# client_board.net
KiCad netlist of a schematic drawn in EAGLE
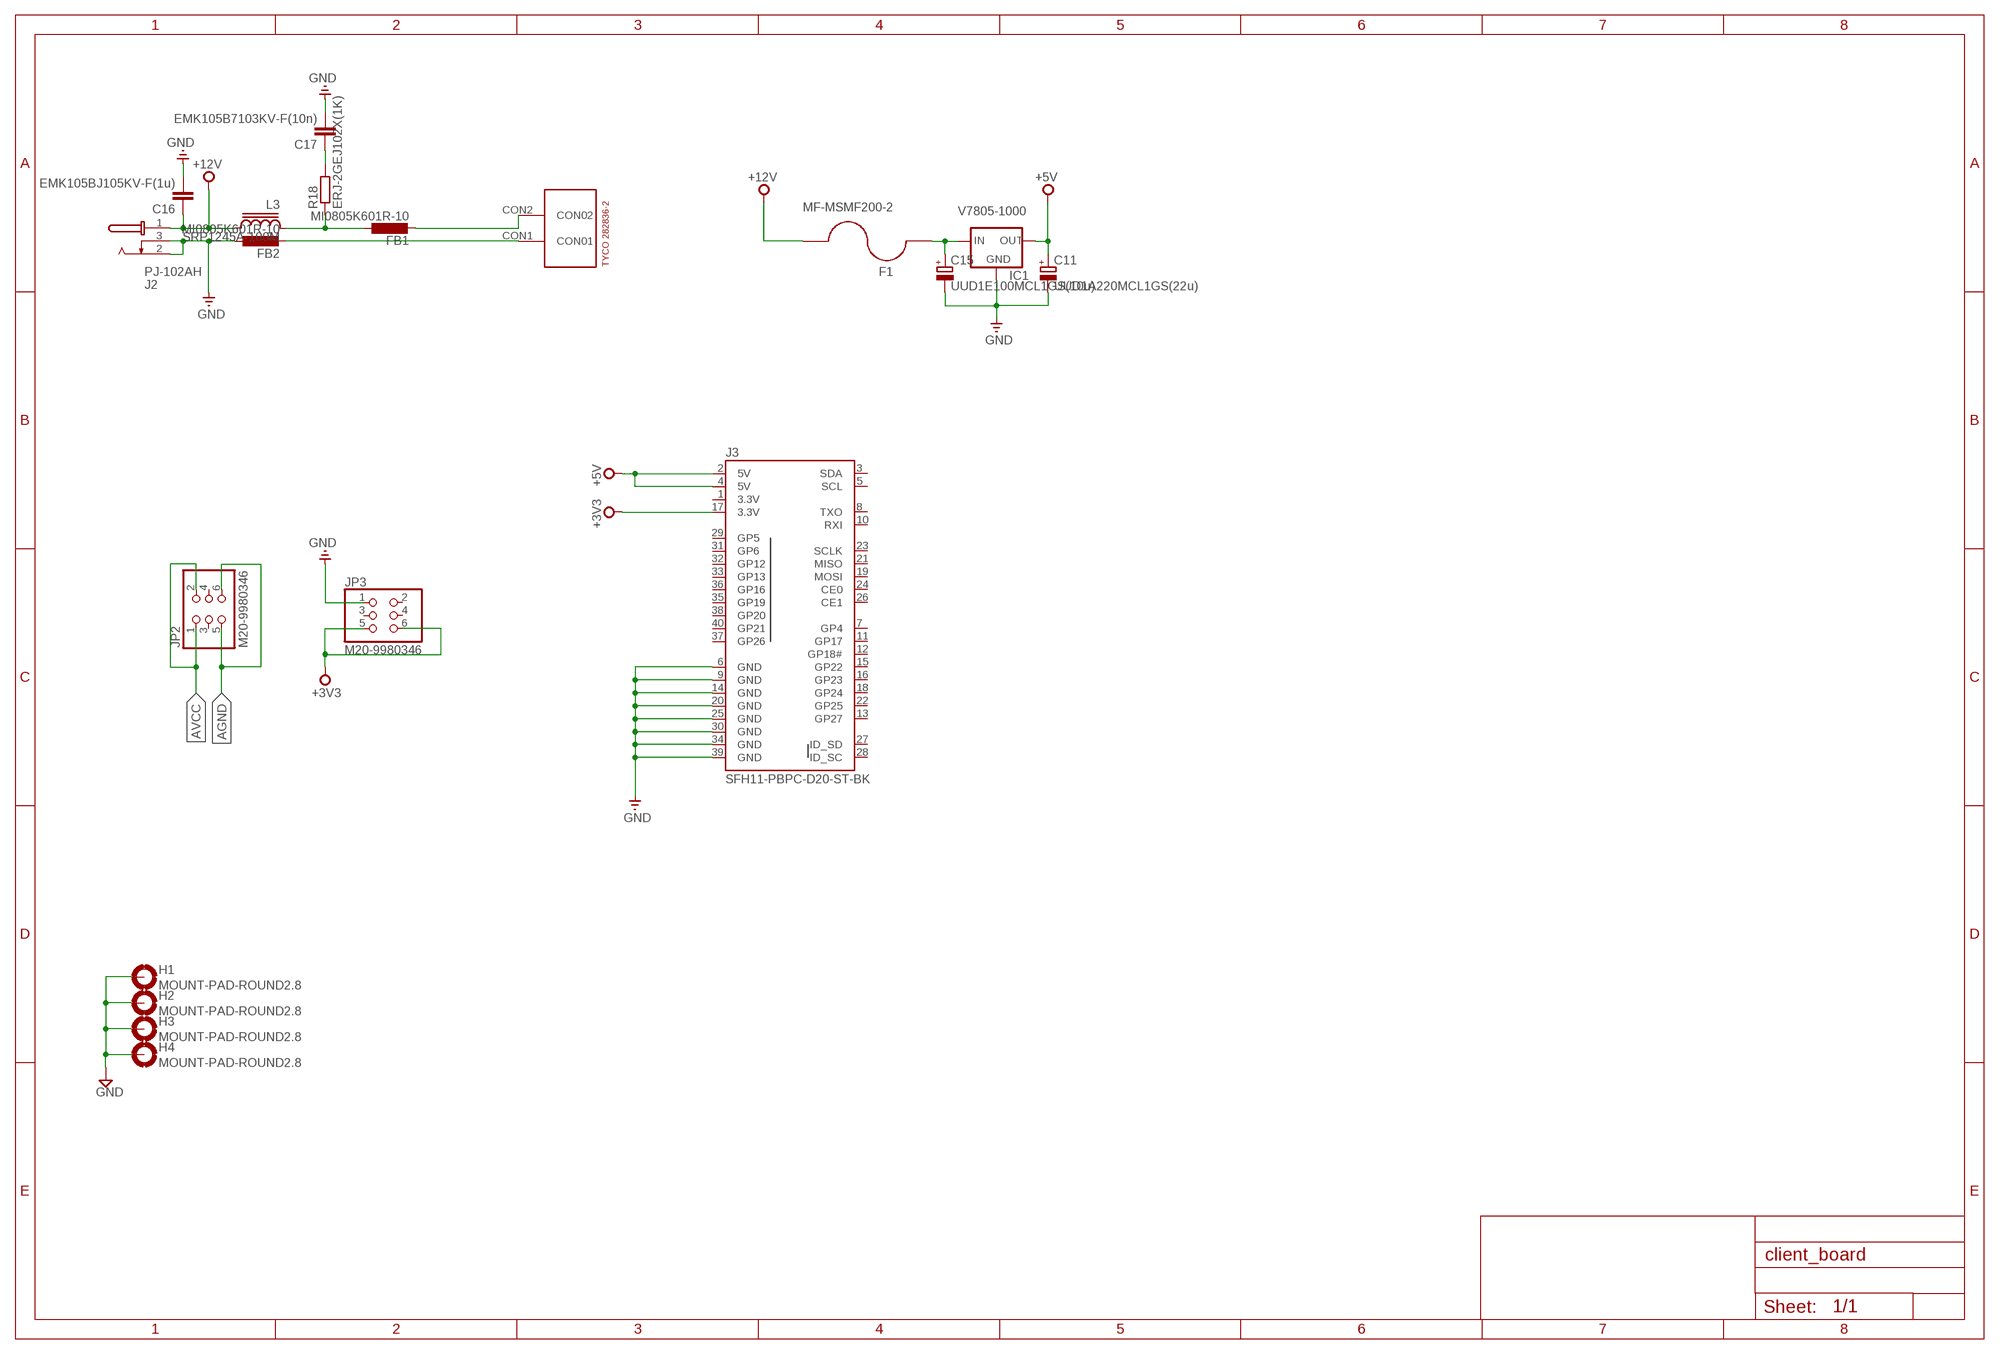
[diagram p0: schematic, sheet 1]

(export (version "E")
  (design (tool "Eeschema 10.0.6"))
  (components
    (comp (ref "C11")
      (value "UUD1A220MCL1GS(22u)")
      (footprint "eagle-import:153CLV-0405")
      (libsource (lib "eagle-import") (part "CPOL-EU153CLV-0405"))
    )
    (comp (ref "C15")
      (value "UUD1E100MCL1GS(10u)")
      (footprint "eagle-import:153CLV-0405")
      (libsource (lib "eagle-import") (part "CPOL-EU153CLV-0405"))
    )
    (comp (ref "C16")
      (value "EMK105BJ105KV-F(1u)")
      (footprint "eagle-import:C0402")
      (libsource (lib "eagle-import") (part "C-EUC0402"))
    )
    (comp (ref "C17")
      (value "EMK105B7103KV-F(10n)")
      (footprint "eagle-import:C0402")
      (libsource (lib "eagle-import") (part "C-EUC0402"))
    )
    (comp (ref "F1")
      (value "MF-MSMF200-2")
      (footprint "eagle-import:1812")
      (fields (field (name "MANUFACTURER") "Bourns Inc.") (field (name "PART_NUMBER") "MF-MSMF075/24-2"))
      (libsource (lib "eagle-import") (part "MF-MSMF?075/24"))
    )
    (comp (ref "FB1")
      (value "MI0805K601R-10")
      (footprint "eagle-import:L5650M")
      (libsource (lib "eagle-import") (part "L-EUL5650M"))
    )
    (comp (ref "FB2")
      (value "MI0805K601R-10")
      (footprint "eagle-import:L5650M")
      (libsource (lib "eagle-import") (part "L-EUL5650M"))
    )
    (comp (ref "H1")
      (value "MOUNT-PAD-ROUND2.8")
      (footprint "eagle-import:2,8-PAD")
      (libsource (lib "eagle-import") (part "MOUNT-PAD-ROUND2.8"))
    )
    (comp (ref "H2")
      (value "MOUNT-PAD-ROUND2.8")
      (footprint "eagle-import:2,8-PAD")
      (libsource (lib "eagle-import") (part "MOUNT-PAD-ROUND2.8"))
    )
    (comp (ref "H3")
      (value "MOUNT-PAD-ROUND2.8")
      (footprint "eagle-import:2,8-PAD")
      (libsource (lib "eagle-import") (part "MOUNT-PAD-ROUND2.8"))
    )
    (comp (ref "H4")
      (value "MOUNT-PAD-ROUND2.8")
      (footprint "eagle-import:2,8-PAD")
      (libsource (lib "eagle-import") (part "MOUNT-PAD-ROUND2.8"))
    )
    (comp (ref "IC1")
      (value "V7805-1000")
      (footprint "eagle-import:DIP_3PIN")
      (libsource (lib "eagle-import") (part "VR_1OUTXX"))
    )
    (comp (ref "J2")
      (value "PJ-102AH")
      (footprint "eagle-import:PJ-102XH")
      (libsource (lib "eagle-import") (part "PJ-102AH/BH"))
    )
    (comp (ref "J3")
      (value "SFH11-PBPC-D20-ST-BK")
      (footprint "eagle-import:2X20-SHROUDED")
      (libsource (lib "eagle-import") (part "RASPBERRYPI-40-PIN-GPIO"))
    )
    (comp (ref "JP2")
      (value "M20-9980346")
      (footprint "eagle-import:2X03")
      (libsource (lib "eagle-import") (part "PINHD-2X3"))
    )
    (comp (ref "JP3")
      (value "M20-9980346")
      (footprint "eagle-import:2X03")
      (libsource (lib "eagle-import") (part "PINHD-2X3"))
    )
    (comp (ref "L3")
      (value "SRP1245A-100M")
      (footprint "eagle-import:SRP1250A")
      (libsource (lib "eagle-import") (part "SRP1250A"))
    )
    (comp (ref "R18")
      (value "ERJ-2GEJ102X(1K)")
      (footprint "eagle-import:R0402")
      (libsource (lib "eagle-import") (part "R-EU_R0402"))
    )
    (comp (ref "U$1")
      (value "282836-2")
      (footprint "eagle-import:282836-2")
      (libsource (lib "eagle-import") (part "282836-2"))
    )
  )
  (nets
    (net (code "1") (name "+3V3") (class "Default")
      (node (ref "J3") (pin "17") (pinfunction "3.3V_17") (pintype "power_in"))
      (node (ref "JP3") (pin "5") (pinfunction "5_5") (pintype "passive"))
      (node (ref "JP3") (pin "6") (pinfunction "6_6") (pintype "passive"))
    )
    (net (code "2") (name "+5V") (class "Default")
      (node (ref "C11") (pin "+") (pinfunction "+_+") (pintype "passive"))
      (node (ref "IC1") (pin "OUT") (pinfunction "OUT_OUT") (pintype "passive"))
      (node (ref "J3") (pin "2") (pinfunction "5V_2") (pintype "power_in"))
      (node (ref "J3") (pin "4") (pinfunction "5V_4") (pintype "power_in"))
    )
    (net (code "3") (name "+12V") (class "Default")
      (node (ref "C16") (pin "1") (pinfunction "1_1") (pintype "passive"))
      (node (ref "F1") (pin "1") (pinfunction "1_1") (pintype "passive"))
      (node (ref "J2") (pin "1") (pinfunction "T_1") (pintype "passive"))
      (node (ref "L3") (pin "2") (pinfunction "2_2") (pintype "passive"))
    )
    (net (code "4") (name "/3.3V") (class "Default")
      (node (ref "J3") (pin "1") (pinfunction "3.3V_1") (pintype "power_in"))
    )
    (net (code "5") (name "AGND") (class "Default")
      (node (ref "FB2") (pin "2") (pinfunction "2_2") (pintype "passive"))
      (node (ref "JP2") (pin "5") (pinfunction "5_5") (pintype "passive"))
      (node (ref "JP2") (pin "6") (pinfunction "6_6") (pintype "passive"))
      (node (ref "U$1") (pin "CON1") (pinfunction "CON01_CON1") (pintype "bidirectional"))
    )
    (net (code "6") (name "AVCC") (class "Default")
      (node (ref "FB1") (pin "2") (pinfunction "2_2") (pintype "passive"))
      (node (ref "JP2") (pin "1") (pinfunction "1_1") (pintype "passive"))
      (node (ref "JP2") (pin "2") (pinfunction "2_2") (pintype "passive"))
      (node (ref "U$1") (pin "CON2") (pinfunction "CON02_CON2") (pintype "bidirectional"))
    )
    (net (code "7") (name "GND") (class "Default")
      (node (ref "C11") (pin "-") (pinfunction "-_-") (pintype "passive"))
      (node (ref "C15") (pin "-") (pinfunction "-_-") (pintype "passive"))
      (node (ref "C16") (pin "2") (pinfunction "2_2") (pintype "passive"))
      (node (ref "C17") (pin "2") (pinfunction "2_2") (pintype "passive"))
      (node (ref "FB2") (pin "1") (pinfunction "1_1") (pintype "passive"))
      (node (ref "H1") (pin "B2,8") (pinfunction "MOUNT_B2,8") (pintype "passive"))
      (node (ref "H2") (pin "B2,8") (pinfunction "MOUNT_B2,8") (pintype "passive"))
      (node (ref "H3") (pin "B2,8") (pinfunction "MOUNT_B2,8") (pintype "passive"))
      (node (ref "H4") (pin "B2,8") (pinfunction "MOUNT_B2,8") (pintype "passive"))
      (node (ref "IC1") (pin "GND") (pinfunction "GND_GND") (pintype "input"))
      (node (ref "J2") (pin "2") (pinfunction "S_2") (pintype "passive"))
      (node (ref "J2") (pin "3") (pinfunction "SS_3") (pintype "passive"))
      (node (ref "J3") (pin "14") (pinfunction "GND_14") (pintype "power_in"))
      (node (ref "J3") (pin "20") (pinfunction "GND_20") (pintype "power_in"))
      (node (ref "J3") (pin "25") (pinfunction "GND_25") (pintype "power_in"))
      (node (ref "J3") (pin "30") (pinfunction "GND_30") (pintype "power_in"))
      (node (ref "J3") (pin "34") (pinfunction "GND_34") (pintype "power_in"))
      (node (ref "J3") (pin "39") (pinfunction "GND_39") (pintype "power_in"))
      (node (ref "J3") (pin "6") (pinfunction "GND_6") (pintype "power_in"))
      (node (ref "J3") (pin "9") (pinfunction "GND_9") (pintype "power_in"))
      (node (ref "JP3") (pin "1") (pinfunction "1_1") (pintype "passive"))
    )
    (net (code "8") (name "Net-(C15-Pad+)") (class "Default")
      (node (ref "C15") (pin "+") (pinfunction "+_+") (pintype "passive"))
      (node (ref "F1") (pin "2") (pinfunction "2_2") (pintype "passive"))
      (node (ref "IC1") (pin "IN") (pinfunction "IN_IN") (pintype "input"))
    )
    (net (code "9") (name "Net-(C17-Pad1)") (class "Default")
      (node (ref "C17") (pin "1") (pinfunction "1_1") (pintype "passive"))
      (node (ref "R18") (pin "2") (pinfunction "2_2") (pintype "passive"))
    )
    (net (code "10") (name "Net-(FB1-Pad1)") (class "Default")
      (node (ref "FB1") (pin "1") (pinfunction "1_1") (pintype "passive"))
      (node (ref "L3") (pin "1") (pinfunction "1_1") (pintype "passive"))
      (node (ref "R18") (pin "1") (pinfunction "1_1") (pintype "passive"))
    )
    (net (code "11") (name "unconnected-(J3-CE0-Pad24)") (class "Default")
      (node (ref "J3") (pin "24") (pinfunction "CE0_24") (pintype "output"))
    )
    (net (code "12") (name "unconnected-(J3-CE1-Pad26)") (class "Default")
      (node (ref "J3") (pin "26") (pinfunction "CE1_26") (pintype "output"))
    )
    (net (code "13") (name "unconnected-(J3-GP4-Pad7)") (class "Default")
      (node (ref "J3") (pin "7") (pinfunction "GP4_7") (pintype "bidirectional"))
    )
    (net (code "14") (name "unconnected-(J3-GP5-Pad29)") (class "Default")
      (node (ref "J3") (pin "29") (pinfunction "GP5_29") (pintype "bidirectional"))
    )
    (net (code "15") (name "unconnected-(J3-GP6-Pad31)") (class "Default")
      (node (ref "J3") (pin "31") (pinfunction "GP6_31") (pintype "bidirectional"))
    )
    (net (code "16") (name "unconnected-(J3-GP12-Pad32)") (class "Default")
      (node (ref "J3") (pin "32") (pinfunction "GP12_32") (pintype "bidirectional"))
    )
    (net (code "17") (name "unconnected-(J3-GP13-Pad33)") (class "Default")
      (node (ref "J3") (pin "33") (pinfunction "GP13_33") (pintype "bidirectional"))
    )
    (net (code "18") (name "unconnected-(J3-GP16-Pad36)") (class "Default")
      (node (ref "J3") (pin "36") (pinfunction "GP16_36") (pintype "bidirectional"))
    )
    (net (code "19") (name "unconnected-(J3-GP17-Pad11)") (class "Default")
      (node (ref "J3") (pin "11") (pinfunction "GP17_11") (pintype "bidirectional"))
    )
    (net (code "20") (name "unconnected-(J3-GP18#-Pad12)") (class "Default")
      (node (ref "J3") (pin "12") (pinfunction "GP18#_12") (pintype "bidirectional"))
    )
    (net (code "21") (name "unconnected-(J3-GP19-Pad35)") (class "Default")
      (node (ref "J3") (pin "35") (pinfunction "GP19_35") (pintype "bidirectional"))
    )
    (net (code "22") (name "unconnected-(J3-GP20-Pad38)") (class "Default")
      (node (ref "J3") (pin "38") (pinfunction "GP20_38") (pintype "bidirectional"))
    )
    (net (code "23") (name "unconnected-(J3-GP21-Pad40)") (class "Default")
      (node (ref "J3") (pin "40") (pinfunction "GP21_40") (pintype "bidirectional"))
    )
    (net (code "24") (name "unconnected-(J3-GP22-Pad15)") (class "Default")
      (node (ref "J3") (pin "15") (pinfunction "GP22_15") (pintype "bidirectional"))
    )
    (net (code "25") (name "unconnected-(J3-GP23-Pad16)") (class "Default")
      (node (ref "J3") (pin "16") (pinfunction "GP23_16") (pintype "bidirectional"))
    )
    (net (code "26") (name "unconnected-(J3-GP24-Pad18)") (class "Default")
      (node (ref "J3") (pin "18") (pinfunction "GP24_18") (pintype "bidirectional"))
    )
    (net (code "27") (name "unconnected-(J3-GP25-Pad22)") (class "Default")
      (node (ref "J3") (pin "22") (pinfunction "GP25_22") (pintype "bidirectional"))
    )
    (net (code "28") (name "unconnected-(J3-GP26-Pad37)") (class "Default")
      (node (ref "J3") (pin "37") (pinfunction "GP26_37") (pintype "bidirectional"))
    )
    (net (code "29") (name "unconnected-(J3-GP27-Pad13)") (class "Default")
      (node (ref "J3") (pin "13") (pinfunction "GP27_13") (pintype "bidirectional"))
    )
    (net (code "30") (name "unconnected-(J3-ID_SC-Pad28)") (class "Default")
      (node (ref "J3") (pin "28") (pinfunction "ID_SC_28") (pintype "bidirectional"))
    )
    (net (code "31") (name "unconnected-(J3-ID_SD-Pad27)") (class "Default")
      (node (ref "J3") (pin "27") (pinfunction "ID_SD_27") (pintype "bidirectional"))
    )
    (net (code "32") (name "unconnected-(J3-MISO-Pad21)") (class "Default")
      (node (ref "J3") (pin "21") (pinfunction "MISO_21") (pintype "input"))
    )
    (net (code "33") (name "unconnected-(J3-MOSI-Pad19)") (class "Default")
      (node (ref "J3") (pin "19") (pinfunction "MOSI_19") (pintype "output"))
    )
    (net (code "34") (name "unconnected-(J3-RXI-Pad10)") (class "Default")
      (node (ref "J3") (pin "10") (pinfunction "RXI_10") (pintype "input"))
    )
    (net (code "35") (name "unconnected-(J3-SCL-Pad5)") (class "Default")
      (node (ref "J3") (pin "5") (pinfunction "SCL_5") (pintype "bidirectional"))
    )
    (net (code "36") (name "unconnected-(J3-SCLK-Pad23)") (class "Default")
      (node (ref "J3") (pin "23") (pinfunction "SCLK_23") (pintype "output"))
    )
    (net (code "37") (name "unconnected-(J3-SDA-Pad3)") (class "Default")
      (node (ref "J3") (pin "3") (pinfunction "SDA_3") (pintype "bidirectional"))
    )
    (net (code "38") (name "unconnected-(J3-TXO-Pad8)") (class "Default")
      (node (ref "J3") (pin "8") (pinfunction "TXO_8") (pintype "output"))
    )
    (net (code "39") (name "unconnected-(JP2-Pad3)") (class "Default")
      (node (ref "JP2") (pin "3") (pinfunction "3_3") (pintype "passive"))
    )
    (net (code "40") (name "unconnected-(JP2-Pad4)") (class "Default")
      (node (ref "JP2") (pin "4") (pinfunction "4_4") (pintype "passive"))
    )
    (net (code "41") (name "unconnected-(JP3-Pad2)") (class "Default")
      (node (ref "JP3") (pin "2") (pinfunction "2_2") (pintype "passive"))
    )
    (net (code "42") (name "unconnected-(JP3-Pad3)") (class "Default")
      (node (ref "JP3") (pin "3") (pinfunction "3_3") (pintype "passive"))
    )
    (net (code "43") (name "unconnected-(JP3-Pad4)") (class "Default")
      (node (ref "JP3") (pin "4") (pinfunction "4_4") (pintype "passive"))
    )
  )
)
